# STM32_Brain.net
KiCad netlist of a schematic drawn in Altium Designer
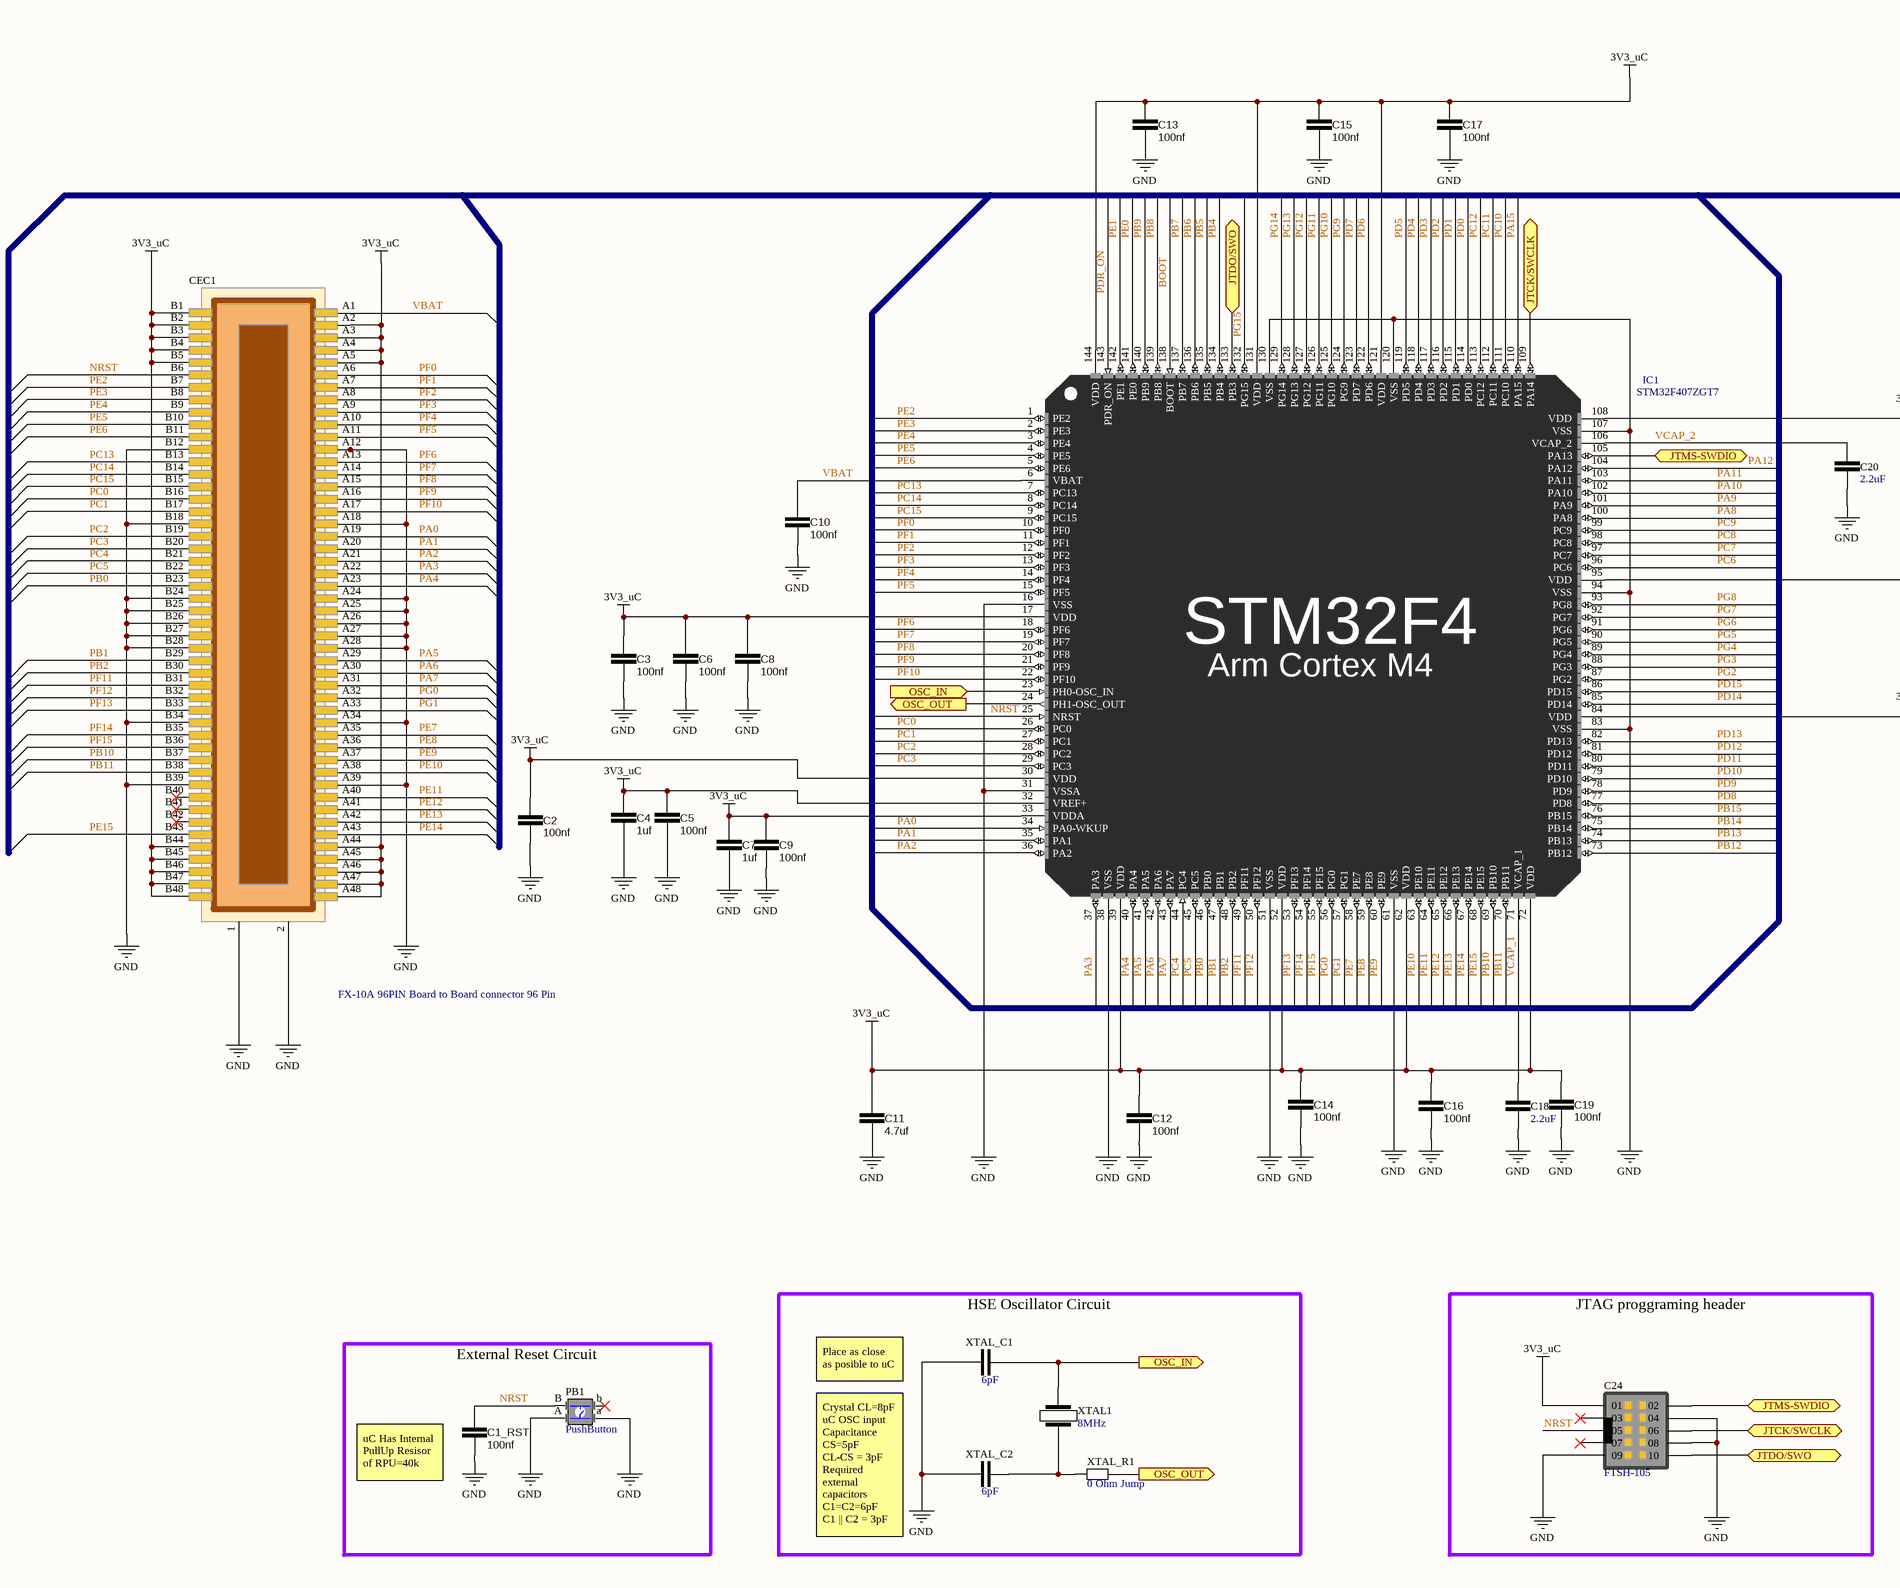
[diagram p0: STM32_Brain.SchDoc, left]
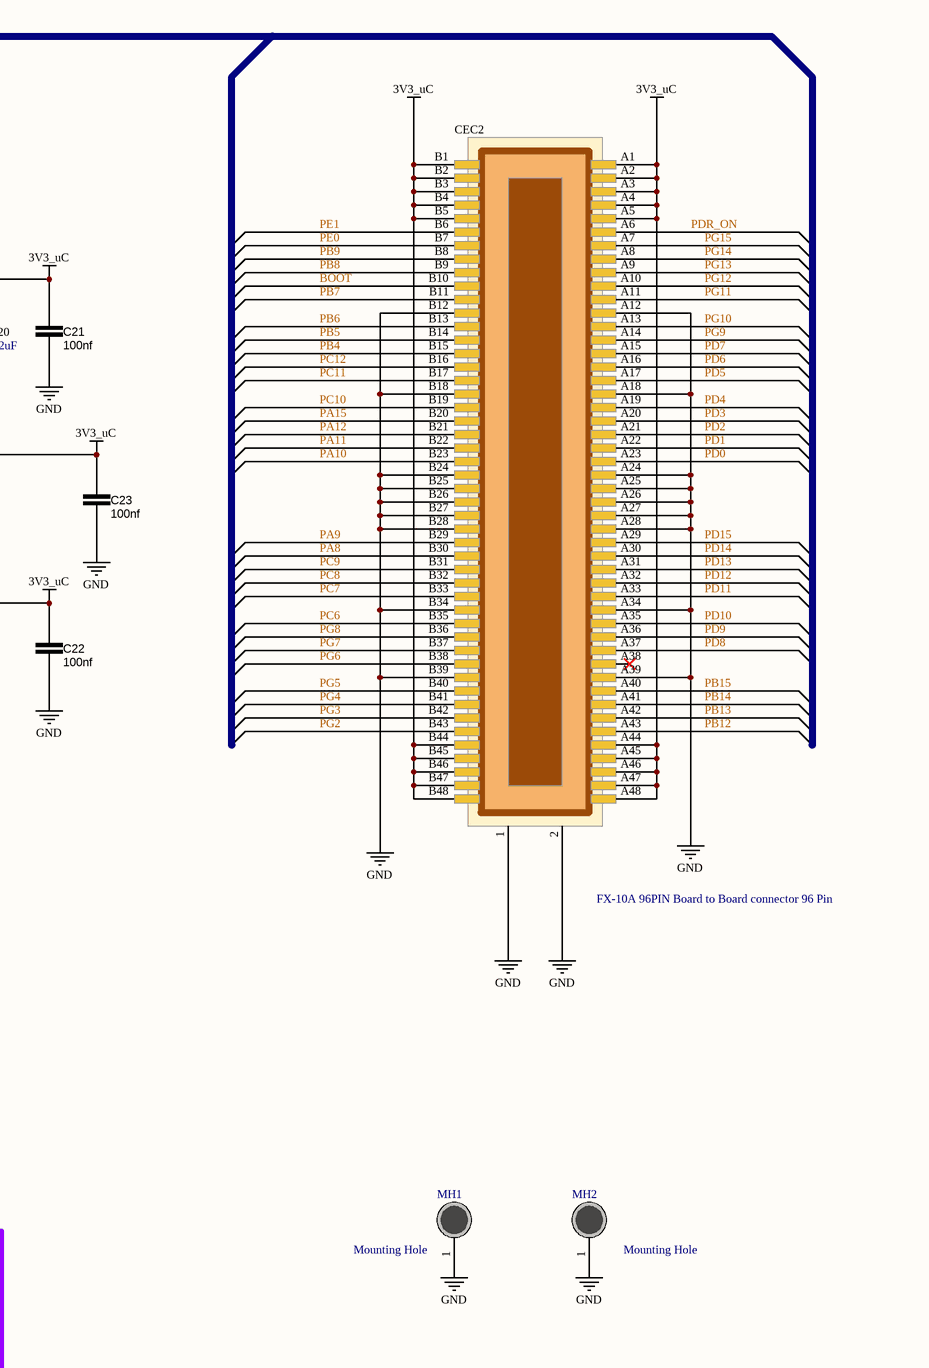
[diagram p1: STM32_Brain.SchDoc, right]

(export (version "E")
  (design (tool "Eeschema 10.0.6"))
  (components
    (comp (ref "C1_RST")
      (value "100nf")
      (footprint "CAP_0603")
      (description "CAP CER 100nF 0603 25V X7R")
      (libsource (lib "CapacitorsIntegrated") (part "0000007"))
    )
    (comp (ref "C2")
      (value "100nf")
      (footprint "CAP_0603")
      (description "CAP CER 100nF 0603 25V X7R")
      (libsource (lib "CapacitorsIntegrated") (part "0000007"))
    )
    (comp (ref "C3")
      (value "100nf")
      (footprint "CAP_0603")
      (description "CAP CER 100nF 0603 25V X7R")
      (libsource (lib "CapacitorsIntegrated") (part "0000007"))
    )
    (comp (ref "C4")
      (value "1uf")
      (footprint "CAP_0603")
      (description "CAP CER 1uF 0603 16V X7R")
      (fields (field (name "DIGIKEY PART NUMBER") "1276-1019-2-ND"))
      (libsource (lib "CapacitorsIntegrated") (part "0000009"))
    )
    (comp (ref "C5")
      (value "100nf")
      (footprint "CAP_0603")
      (description "CAP CER 100nF 0603 25V X7R")
      (libsource (lib "CapacitorsIntegrated") (part "0000007"))
    )
    (comp (ref "C6")
      (value "100nf")
      (footprint "CAP_0603")
      (description "CAP CER 100nF 0603 25V X7R")
      (libsource (lib "CapacitorsIntegrated") (part "0000007"))
    )
    (comp (ref "C7")
      (value "1uf")
      (footprint "CAP_0603")
      (description "CAP CER 1uF 0603 16V X7R")
      (fields (field (name "DIGIKEY PART NUMBER") "1276-1019-2-ND"))
      (libsource (lib "CapacitorsIntegrated") (part "0000009"))
    )
    (comp (ref "C8")
      (value "100nf")
      (footprint "CAP_0603")
      (description "CAP CER 100nF 0603 25V X7R")
      (libsource (lib "CapacitorsIntegrated") (part "0000007"))
    )
    (comp (ref "C9")
      (value "100nf")
      (footprint "CAP_0603")
      (description "CAP CER 100nF 0603 25V X7R")
      (libsource (lib "CapacitorsIntegrated") (part "0000007"))
    )
    (comp (ref "C10")
      (value "100nf")
      (footprint "CAP_0603")
      (description "CAP CER 100nF 0603 25V X7R")
      (libsource (lib "CapacitorsIntegrated") (part "0000007"))
    )
    (comp (ref "C11")
      (value "4.7uf")
      (footprint "CAP_0805")
      (description "CAP CER 4.7uF 0805 25V X5R")
      (libsource (lib "CapacitorsIntegrated") (part "0000003"))
    )
    (comp (ref "C12")
      (value "100nf")
      (footprint "CAP_0603")
      (description "CAP CER 100nF 0603 25V X7R")
      (libsource (lib "CapacitorsIntegrated") (part "0000007"))
    )
    (comp (ref "C13")
      (value "100nf")
      (footprint "CAP_0603")
      (description "CAP CER 100nF 0603 25V X7R")
      (libsource (lib "CapacitorsIntegrated") (part "0000007"))
    )
    (comp (ref "C14")
      (value "100nf")
      (footprint "CAP_0603")
      (description "CAP CER 100nF 0603 25V X7R")
      (libsource (lib "CapacitorsIntegrated") (part "0000007"))
    )
    (comp (ref "C15")
      (value "100nf")
      (footprint "CAP_0603")
      (description "CAP CER 100nF 0603 25V X7R")
      (libsource (lib "CapacitorsIntegrated") (part "0000007"))
    )
    (comp (ref "C16")
      (value "100nf")
      (footprint "CAP_0603")
      (description "CAP CER 100nF 0603 25V X7R")
      (libsource (lib "CapacitorsIntegrated") (part "0000007"))
    )
    (comp (ref "C17")
      (value "100nf")
      (footprint "CAP_0603")
      (description "CAP CER 100nF 0603 25V X7R")
      (libsource (lib "CapacitorsIntegrated") (part "0000007"))
    )
    (comp (ref "C18")
      (value "2.2uF")
      (footprint "CAP_0603")
      (description "CAP CER 2.2UF 16V X7S 0603")
      (fields (field (name "DIGIKEY PART NUMBER") "490-12731-1-ND"))
      (libsource (lib "CapacitorsIntegrated") (part "0000014"))
    )
    (comp (ref "C19")
      (value "100nf")
      (footprint "CAP_0603")
      (description "CAP CER 100nF 0603 25V X7R")
      (libsource (lib "CapacitorsIntegrated") (part "0000007"))
    )
    (comp (ref "C20")
      (value "2.2uF")
      (footprint "CAP_0603")
      (description "CAP CER 2.2UF 16V X7S 0603")
      (fields (field (name "DIGIKEY PART NUMBER") "490-12731-1-ND"))
      (libsource (lib "CapacitorsIntegrated") (part "0000014"))
    )
    (comp (ref "C21")
      (value "100nf")
      (footprint "CAP_0603")
      (description "CAP CER 100nF 0603 25V X7R")
      (libsource (lib "CapacitorsIntegrated") (part "0000007"))
    )
    (comp (ref "C22")
      (value "100nf")
      (footprint "CAP_0603")
      (description "CAP CER 100nF 0603 25V X7R")
      (libsource (lib "CapacitorsIntegrated") (part "0000007"))
    )
    (comp (ref "C23")
      (value "100nf")
      (footprint "CAP_0603")
      (description "CAP CER 100nF 0603 25V X7R")
      (libsource (lib "CapacitorsIntegrated") (part "0000007"))
    )
    (comp (ref "C24")
      (value "FTSH-105")
      (footprint "10 Position SMT Connector")
      (description "FTSH-105-01-F-DV-K - CONN HEADER SMD 10POS 1.27MM")
      (fields
        (field (name "DIGIKEY PART NUMBER") "SAM8796-ND")
        (field (name "MOUSER PART NUMBER") "200-FTSH10501LDVKPTR")
      )
      (libsource (lib "ElectroMechanical") (part "00000009"))
    )
    (comp (ref "CEC1")
      (value "FX-10A 96PIN Board to Board connector 96 Pin")
      (footprint "Board To Board Connector")
      (description "CONN RCPT 96POS SMD GOLD")
      (fields (field (name "DIGIKEY PART NUMBER") "H122463-ND"))
      (libsource (lib "ElectroMechanical") (part "00000008"))
    )
    (comp (ref "CEC2")
      (value "FX-10A 96PIN Board to Board connector 96 Pin")
      (footprint "Board To Board Connector")
      (description "CONN RCPT 96POS SMD GOLD")
      (fields (field (name "DIGIKEY PART NUMBER") "H122463-ND"))
      (libsource (lib "ElectroMechanical") (part "00000008"))
    )
    (comp (ref "IC1")
      (value "STM32F407ZGT7")
      (footprint "TSQFP50P2260X2260X160-144N")
      (libsource (lib "IntegratedCircuits") (part "STM32F407ZGT7"))
    )
    (comp (ref "MH1")
      (value "Mounting Hole")
      (footprint "HOLE-3mm")
      (description "Mounting Hole 3mm")
      (libsource (lib "ElectroMechanical") (part "00000006"))
    )
    (comp (ref "MH2")
      (value "Mounting Hole")
      (footprint "HOLE-3mm")
      (description "Mounting Hole 3mm")
      (libsource (lib "ElectroMechanical") (part "00000006"))
    )
    (comp (ref "PB1")
      (value "PushButton")
      (footprint "Tactile Switch")
      (description "SWITCH TACTILE SPST-NO 0.02A 15V")
      (fields (field (name "DIGIKEY PART NUMBER") "P12937SCT-ND"))
      (libsource (lib "ElectroMechanical") (part "00000010"))
    )
    (comp (ref "XTAL1")
      (value "8MHz")
      (footprint "XTAL-SMD")
      (description "CRYSTAL 8.0000MHZ 8PF SMD")
      (fields (field (name "DIGIKEY PART NUMBER") "644-STDCSU1-8MTR-ND"))
      (libsource (lib "Miscellaneous_Lib1") (part "00000004"))
    )
    (comp (ref "XTAL_C1")
      (value "6pF")
      (footprint "CAP_0402")
      (description "CAP CER 6PF 25V C0G/NP0 0402")
      (fields (field (name "DIGIKEY PART NUMBER") "399-CBR04C609D3GACCT-ND"))
      (libsource (lib "CapacitorsIntegrated") (part "0000016"))
    )
    (comp (ref "XTAL_C2")
      (value "6pF")
      (footprint "CAP_0402")
      (description "CAP CER 6PF 25V C0G/NP0 0402")
      (fields (field (name "DIGIKEY PART NUMBER") "399-CBR04C609D3GACCT-ND"))
      (libsource (lib "CapacitorsIntegrated") (part "0000016"))
    )
    (comp (ref "XTAL_R1")
      (value "0 Ohm Jump")
      (footprint "RES_0402")
      (description "RES SMD 0 OHM JUMPER 1/10W 0402")
      (fields (field (name "DIGIKEY PART NUMBER") "P0.0JCT-ND"))
      (libsource (lib "ResistorsIntegrated") (part "R000008"))
    )
  )
  (nets
    (net (code "1") (name "/BOOT") (class "Default")
      (node (ref "CEC2") (pin "B10") (pinfunction "10_B10") (pintype "passive"))
      (node (ref "IC1") (pin "138") (pinfunction "BOOT_138") (pintype "input"))
    )
    (net (code "2") (name "/JTCK{slash}SWCLK") (class "Default")
      (node (ref "C24") (pin "06") (pinfunction "06_06") (pintype "passive"))
      (node (ref "IC1") (pin "109") (pinfunction "PA14_109") (pintype "bidirectional"))
    )
    (net (code "3") (name "/JTDO{slash}SWO") (class "Default")
      (node (ref "C24") (pin "10") (pinfunction "10_10") (pintype "passive"))
      (node (ref "IC1") (pin "133") (pinfunction "PB3_133") (pintype "bidirectional"))
    )
    (net (code "4") (name "/JTMS-SWDIO") (class "Default")
      (node (ref "C24") (pin "02") (pinfunction "02_02") (pintype "passive"))
      (node (ref "IC1") (pin "105") (pinfunction "PA13_105") (pintype "bidirectional"))
    )
    (net (code "5") (name "/NRST") (class "Default")
      (node (ref "C1_RST") (pin "2") (pinfunction "2_2") (pintype "passive"))
      (node (ref "C24") (pin "05") (pinfunction "05_05") (pintype "passive"))
      (node (ref "CEC1") (pin "B6") (pinfunction "6_B6") (pintype "passive"))
      (node (ref "IC1") (pin "25") (pinfunction "NRST_25") (pintype "input"))
      (node (ref "PB1") (pin "B") (pinfunction "B_B") (pintype "passive"))
    )
    (net (code "6") (name "/OSC_IN") (class "Default")
      (node (ref "IC1") (pin "23") (pinfunction "PH0-OSC_IN_23") (pintype "input"))
      (node (ref "XTAL1") (pin "2") (pinfunction "2_2") (pintype "passive"))
      (node (ref "XTAL_C1") (pin "2") (pinfunction "2_2") (pintype "passive"))
    )
    (net (code "7") (name "/OSC_OUT") (class "Default")
      (node (ref "IC1") (pin "24") (pinfunction "PH1-OSC_OUT_24") (pintype "output"))
      (node (ref "XTAL_R1") (pin "2") (pinfunction "2_2") (pintype "passive"))
    )
    (net (code "8") (name "/PA0") (class "Default")
      (node (ref "CEC1") (pin "A19") (pinfunction "19_A19") (pintype "passive"))
      (node (ref "IC1") (pin "34") (pinfunction "PA0-WKUP_34") (pintype "input"))
    )
    (net (code "9") (name "/PA1") (class "Default")
      (node (ref "CEC1") (pin "A20") (pinfunction "20_A20") (pintype "passive"))
      (node (ref "IC1") (pin "35") (pinfunction "PA1_35") (pintype "bidirectional"))
    )
    (net (code "10") (name "/PA2") (class "Default")
      (node (ref "CEC1") (pin "A21") (pinfunction "21_A21") (pintype "passive"))
      (node (ref "IC1") (pin "36") (pinfunction "PA2_36") (pintype "bidirectional"))
    )
    (net (code "11") (name "/PA3") (class "Default")
      (node (ref "CEC1") (pin "A22") (pinfunction "22_A22") (pintype "passive"))
      (node (ref "IC1") (pin "37") (pinfunction "PA3_37") (pintype "bidirectional"))
    )
    (net (code "12") (name "/PA4") (class "Default")
      (node (ref "CEC1") (pin "A23") (pinfunction "23_A23") (pintype "passive"))
      (node (ref "IC1") (pin "40") (pinfunction "PA4_40") (pintype "bidirectional"))
    )
    (net (code "13") (name "/PA5") (class "Default")
      (node (ref "CEC1") (pin "A29") (pinfunction "29_A29") (pintype "passive"))
      (node (ref "IC1") (pin "41") (pinfunction "PA5_41") (pintype "bidirectional"))
    )
    (net (code "14") (name "/PA6") (class "Default")
      (node (ref "CEC1") (pin "A30") (pinfunction "30_A30") (pintype "passive"))
      (node (ref "IC1") (pin "42") (pinfunction "PA6_42") (pintype "bidirectional"))
    )
    (net (code "15") (name "/PA7") (class "Default")
      (node (ref "CEC1") (pin "A31") (pinfunction "31_A31") (pintype "passive"))
      (node (ref "IC1") (pin "43") (pinfunction "PA7_43") (pintype "bidirectional"))
    )
    (net (code "16") (name "/PA8") (class "Default")
      (node (ref "CEC2") (pin "B30") (pinfunction "30_B30") (pintype "passive"))
      (node (ref "IC1") (pin "100") (pinfunction "PA8_100") (pintype "bidirectional"))
    )
    (net (code "17") (name "/PA9") (class "Default")
      (node (ref "CEC2") (pin "B29") (pinfunction "29_B29") (pintype "passive"))
      (node (ref "IC1") (pin "101") (pinfunction "PA9_101") (pintype "bidirectional"))
    )
    (net (code "18") (name "/PA10") (class "Default")
      (node (ref "CEC2") (pin "B23") (pinfunction "23_B23") (pintype "passive"))
      (node (ref "IC1") (pin "102") (pinfunction "PA10_102") (pintype "bidirectional"))
    )
    (net (code "19") (name "/PA11") (class "Default")
      (node (ref "CEC2") (pin "B22") (pinfunction "22_B22") (pintype "passive"))
      (node (ref "IC1") (pin "103") (pinfunction "PA11_103") (pintype "bidirectional"))
    )
    (net (code "20") (name "/PA12") (class "Default")
      (node (ref "CEC2") (pin "B21") (pinfunction "21_B21") (pintype "passive"))
      (node (ref "IC1") (pin "104") (pinfunction "PA12_104") (pintype "bidirectional"))
    )
    (net (code "21") (name "/PA15") (class "Default")
      (node (ref "CEC2") (pin "B20") (pinfunction "20_B20") (pintype "passive"))
      (node (ref "IC1") (pin "110") (pinfunction "PA15_110") (pintype "bidirectional"))
    )
    (net (code "22") (name "/PB0") (class "Default")
      (node (ref "CEC1") (pin "B23") (pinfunction "23_B23") (pintype "passive"))
      (node (ref "IC1") (pin "46") (pinfunction "PB0_46") (pintype "bidirectional"))
    )
    (net (code "23") (name "/PB1") (class "Default")
      (node (ref "CEC1") (pin "B29") (pinfunction "29_B29") (pintype "passive"))
      (node (ref "IC1") (pin "47") (pinfunction "PB1_47") (pintype "bidirectional"))
    )
    (net (code "24") (name "/PB2") (class "Default")
      (node (ref "CEC1") (pin "B30") (pinfunction "30_B30") (pintype "passive"))
      (node (ref "IC1") (pin "48") (pinfunction "PB2_48") (pintype "bidirectional"))
    )
    (net (code "25") (name "/PB4") (class "Default")
      (node (ref "CEC2") (pin "B15") (pinfunction "15_B15") (pintype "passive"))
      (node (ref "IC1") (pin "134") (pinfunction "PB4_134") (pintype "bidirectional"))
    )
    (net (code "26") (name "/PB5") (class "Default")
      (node (ref "CEC2") (pin "B14") (pinfunction "14_B14") (pintype "passive"))
      (node (ref "IC1") (pin "135") (pinfunction "PB5_135") (pintype "bidirectional"))
    )
    (net (code "27") (name "/PB6") (class "Default")
      (node (ref "CEC2") (pin "B13") (pinfunction "13_B13") (pintype "passive"))
      (node (ref "IC1") (pin "136") (pinfunction "PB6_136") (pintype "bidirectional"))
    )
    (net (code "28") (name "/PB7") (class "Default")
      (node (ref "CEC2") (pin "B11") (pinfunction "11_B11") (pintype "passive"))
      (node (ref "IC1") (pin "137") (pinfunction "PB7_137") (pintype "bidirectional"))
    )
    (net (code "29") (name "/PB8") (class "Default")
      (node (ref "CEC2") (pin "B9") (pinfunction "9_B9") (pintype "passive"))
      (node (ref "IC1") (pin "139") (pinfunction "PB8_139") (pintype "bidirectional"))
    )
    (net (code "30") (name "/PB9") (class "Default")
      (node (ref "CEC2") (pin "B8") (pinfunction "8_B8") (pintype "passive"))
      (node (ref "IC1") (pin "140") (pinfunction "PB9_140") (pintype "bidirectional"))
    )
    (net (code "31") (name "/PB10") (class "Default")
      (node (ref "CEC1") (pin "B37") (pinfunction "37_B37") (pintype "passive"))
      (node (ref "IC1") (pin "69") (pinfunction "PB10_69") (pintype "bidirectional"))
    )
    (net (code "32") (name "/PB11") (class "Default")
      (node (ref "CEC1") (pin "B38") (pinfunction "38_B38") (pintype "passive"))
      (node (ref "IC1") (pin "70") (pinfunction "PB11_70") (pintype "bidirectional"))
    )
    (net (code "33") (name "/PB12") (class "Default")
      (node (ref "CEC2") (pin "A43") (pinfunction "43_A43") (pintype "passive"))
      (node (ref "IC1") (pin "73") (pinfunction "PB12_73") (pintype "bidirectional"))
    )
    (net (code "34") (name "/PB13") (class "Default")
      (node (ref "CEC2") (pin "A42") (pinfunction "42_A42") (pintype "passive"))
      (node (ref "IC1") (pin "74") (pinfunction "PB13_74") (pintype "bidirectional"))
    )
    (net (code "35") (name "/PB14") (class "Default")
      (node (ref "CEC2") (pin "A41") (pinfunction "41_A41") (pintype "passive"))
      (node (ref "IC1") (pin "75") (pinfunction "PB14_75") (pintype "bidirectional"))
    )
    (net (code "36") (name "/PB15") (class "Default")
      (node (ref "CEC2") (pin "A40") (pinfunction "40_A40") (pintype "passive"))
      (node (ref "IC1") (pin "76") (pinfunction "PB15_76") (pintype "bidirectional"))
    )
    (net (code "37") (name "/PC0") (class "Default")
      (node (ref "CEC1") (pin "B16") (pinfunction "16_B16") (pintype "passive"))
      (node (ref "IC1") (pin "26") (pinfunction "PC0_26") (pintype "bidirectional"))
    )
    (net (code "38") (name "/PC1") (class "Default")
      (node (ref "CEC1") (pin "B17") (pinfunction "17_B17") (pintype "passive"))
      (node (ref "IC1") (pin "27") (pinfunction "PC1_27") (pintype "bidirectional"))
    )
    (net (code "39") (name "/PC2") (class "Default")
      (node (ref "CEC1") (pin "B19") (pinfunction "19_B19") (pintype "passive"))
      (node (ref "IC1") (pin "28") (pinfunction "PC2_28") (pintype "bidirectional"))
    )
    (net (code "40") (name "/PC3") (class "Default")
      (node (ref "CEC1") (pin "B20") (pinfunction "20_B20") (pintype "passive"))
      (node (ref "IC1") (pin "29") (pinfunction "PC3_29") (pintype "bidirectional"))
    )
    (net (code "41") (name "/PC4") (class "Default")
      (node (ref "CEC1") (pin "B21") (pinfunction "21_B21") (pintype "passive"))
      (node (ref "IC1") (pin "44") (pinfunction "PC4_44") (pintype "input"))
    )
    (net (code "42") (name "/PC5") (class "Default")
      (node (ref "CEC1") (pin "B22") (pinfunction "22_B22") (pintype "passive"))
      (node (ref "IC1") (pin "45") (pinfunction "PC5_45") (pintype "bidirectional"))
    )
    (net (code "43") (name "/PC6") (class "Default")
      (node (ref "CEC2") (pin "B35") (pinfunction "35_B35") (pintype "passive"))
      (node (ref "IC1") (pin "96") (pinfunction "PC6_96") (pintype "bidirectional"))
    )
    (net (code "44") (name "/PC7") (class "Default")
      (node (ref "CEC2") (pin "B33") (pinfunction "33_B33") (pintype "passive"))
      (node (ref "IC1") (pin "97") (pinfunction "PC7_97") (pintype "bidirectional"))
    )
    (net (code "45") (name "/PC8") (class "Default")
      (node (ref "CEC2") (pin "B32") (pinfunction "32_B32") (pintype "passive"))
      (node (ref "IC1") (pin "98") (pinfunction "PC8_98") (pintype "bidirectional"))
    )
    (net (code "46") (name "/PC9") (class "Default")
      (node (ref "CEC2") (pin "B31") (pinfunction "31_B31") (pintype "passive"))
      (node (ref "IC1") (pin "99") (pinfunction "PC9_99") (pintype "bidirectional"))
    )
    (net (code "47") (name "/PC10") (class "Default")
      (node (ref "CEC2") (pin "B19") (pinfunction "19_B19") (pintype "passive"))
      (node (ref "IC1") (pin "111") (pinfunction "PC10_111") (pintype "bidirectional"))
    )
    (net (code "48") (name "/PC11") (class "Default")
      (node (ref "CEC2") (pin "B17") (pinfunction "17_B17") (pintype "passive"))
      (node (ref "IC1") (pin "112") (pinfunction "PC11_112") (pintype "bidirectional"))
    )
    (net (code "49") (name "/PC12") (class "Default")
      (node (ref "CEC2") (pin "B16") (pinfunction "16_B16") (pintype "passive"))
      (node (ref "IC1") (pin "113") (pinfunction "PC12_113") (pintype "bidirectional"))
    )
    (net (code "50") (name "/PC13") (class "Default")
      (node (ref "CEC1") (pin "B13") (pinfunction "13_B13") (pintype "passive"))
      (node (ref "IC1") (pin "7") (pinfunction "PC13_7") (pintype "bidirectional"))
    )
    (net (code "51") (name "/PC14") (class "Default")
      (node (ref "CEC1") (pin "B14") (pinfunction "14_B14") (pintype "passive"))
      (node (ref "IC1") (pin "8") (pinfunction "PC14_8") (pintype "bidirectional"))
    )
    (net (code "52") (name "/PC15") (class "Default")
      (node (ref "CEC1") (pin "B15") (pinfunction "15_B15") (pintype "passive"))
      (node (ref "IC1") (pin "9") (pinfunction "PC15_9") (pintype "bidirectional"))
    )
    (net (code "53") (name "/PD0") (class "Default")
      (node (ref "CEC2") (pin "A23") (pinfunction "23_A23") (pintype "passive"))
      (node (ref "IC1") (pin "114") (pinfunction "PD0_114") (pintype "bidirectional"))
    )
    (net (code "54") (name "/PD1") (class "Default")
      (node (ref "CEC2") (pin "A22") (pinfunction "22_A22") (pintype "passive"))
      (node (ref "IC1") (pin "115") (pinfunction "PD1_115") (pintype "bidirectional"))
    )
    (net (code "55") (name "/PD2") (class "Default")
      (node (ref "CEC2") (pin "A21") (pinfunction "21_A21") (pintype "passive"))
      (node (ref "IC1") (pin "116") (pinfunction "PD2_116") (pintype "bidirectional"))
    )
    (net (code "56") (name "/PD3") (class "Default")
      (node (ref "CEC2") (pin "A20") (pinfunction "20_A20") (pintype "passive"))
      (node (ref "IC1") (pin "117") (pinfunction "PD3_117") (pintype "bidirectional"))
    )
    (net (code "57") (name "/PD4") (class "Default")
      (node (ref "CEC2") (pin "A19") (pinfunction "19_A19") (pintype "passive"))
      (node (ref "IC1") (pin "118") (pinfunction "PD4_118") (pintype "bidirectional"))
    )
    (net (code "58") (name "/PD5") (class "Default")
      (node (ref "CEC2") (pin "A17") (pinfunction "17_A17") (pintype "passive"))
      (node (ref "IC1") (pin "119") (pinfunction "PD5_119") (pintype "bidirectional"))
    )
    (net (code "59") (name "/PD6") (class "Default")
      (node (ref "CEC2") (pin "A16") (pinfunction "16_A16") (pintype "passive"))
      (node (ref "IC1") (pin "122") (pinfunction "PD6_122") (pintype "bidirectional"))
    )
    (net (code "60") (name "/PD7") (class "Default")
      (node (ref "CEC2") (pin "A15") (pinfunction "15_A15") (pintype "passive"))
      (node (ref "IC1") (pin "123") (pinfunction "PD7_123") (pintype "bidirectional"))
    )
    (net (code "61") (name "/PD8") (class "Default")
      (node (ref "CEC2") (pin "A37") (pinfunction "37_A37") (pintype "passive"))
      (node (ref "IC1") (pin "77") (pinfunction "PD8_77") (pintype "bidirectional"))
    )
    (net (code "62") (name "/PD9") (class "Default")
      (node (ref "CEC2") (pin "A36") (pinfunction "36_A36") (pintype "passive"))
      (node (ref "IC1") (pin "78") (pinfunction "PD9_78") (pintype "bidirectional"))
    )
    (net (code "63") (name "/PD10") (class "Default")
      (node (ref "CEC2") (pin "A35") (pinfunction "35_A35") (pintype "passive"))
      (node (ref "IC1") (pin "79") (pinfunction "PD10_79") (pintype "bidirectional"))
    )
    (net (code "64") (name "/PD11") (class "Default")
      (node (ref "CEC2") (pin "A33") (pinfunction "33_A33") (pintype "passive"))
      (node (ref "IC1") (pin "80") (pinfunction "PD11_80") (pintype "bidirectional"))
    )
    (net (code "65") (name "/PD12") (class "Default")
      (node (ref "CEC2") (pin "A32") (pinfunction "32_A32") (pintype "passive"))
      (node (ref "IC1") (pin "81") (pinfunction "PD12_81") (pintype "bidirectional"))
    )
    (net (code "66") (name "/PD13") (class "Default")
      (node (ref "CEC2") (pin "A31") (pinfunction "31_A31") (pintype "passive"))
      (node (ref "IC1") (pin "82") (pinfunction "PD13_82") (pintype "bidirectional"))
    )
    (net (code "67") (name "/PD14") (class "Default")
      (node (ref "CEC2") (pin "A30") (pinfunction "30_A30") (pintype "passive"))
      (node (ref "IC1") (pin "85") (pinfunction "PD14_85") (pintype "bidirectional"))
    )
    (net (code "68") (name "/PD15") (class "Default")
      (node (ref "CEC2") (pin "A29") (pinfunction "29_A29") (pintype "passive"))
      (node (ref "IC1") (pin "86") (pinfunction "PD15_86") (pintype "bidirectional"))
    )
    (net (code "69") (name "/PDR_ON") (class "Default")
      (node (ref "CEC2") (pin "A6") (pinfunction "6_A6") (pintype "passive"))
      (node (ref "IC1") (pin "143") (pinfunction "PDR_ON_143") (pintype "input"))
    )
    (net (code "70") (name "/PE0") (class "Default")
      (node (ref "CEC2") (pin "B7") (pinfunction "7_B7") (pintype "passive"))
      (node (ref "IC1") (pin "141") (pinfunction "PE0_141") (pintype "bidirectional"))
    )
    (net (code "71") (name "/PE1") (class "Default")
      (node (ref "CEC2") (pin "B6") (pinfunction "6_B6") (pintype "passive"))
      (node (ref "IC1") (pin "142") (pinfunction "PE1_142") (pintype "bidirectional"))
    )
    (net (code "72") (name "/PE2") (class "Default")
      (node (ref "CEC1") (pin "B7") (pinfunction "7_B7") (pintype "passive"))
      (node (ref "IC1") (pin "1") (pinfunction "PE2_1") (pintype "bidirectional"))
    )
    (net (code "73") (name "/PE3") (class "Default")
      (node (ref "CEC1") (pin "B8") (pinfunction "8_B8") (pintype "passive"))
      (node (ref "IC1") (pin "2") (pinfunction "PE3_2") (pintype "bidirectional"))
    )
    (net (code "74") (name "/PE4") (class "Default")
      (node (ref "CEC1") (pin "B9") (pinfunction "9_B9") (pintype "passive"))
      (node (ref "IC1") (pin "3") (pinfunction "PE4_3") (pintype "bidirectional"))
    )
    (net (code "75") (name "/PE5") (class "Default")
      (node (ref "CEC1") (pin "B10") (pinfunction "10_B10") (pintype "passive"))
      (node (ref "IC1") (pin "4") (pinfunction "PE5_4") (pintype "bidirectional"))
    )
    (net (code "76") (name "/PE6") (class "Default")
      (node (ref "CEC1") (pin "B11") (pinfunction "11_B11") (pintype "passive"))
      (node (ref "IC1") (pin "5") (pinfunction "PE6_5") (pintype "bidirectional"))
    )
    (net (code "77") (name "/PE7") (class "Default")
      (node (ref "CEC1") (pin "A35") (pinfunction "35_A35") (pintype "passive"))
      (node (ref "IC1") (pin "58") (pinfunction "PE7_58") (pintype "bidirectional"))
    )
    (net (code "78") (name "/PE8") (class "Default")
      (node (ref "CEC1") (pin "A36") (pinfunction "36_A36") (pintype "passive"))
      (node (ref "IC1") (pin "59") (pinfunction "PE8_59") (pintype "bidirectional"))
    )
    (net (code "79") (name "/PE9") (class "Default")
      (node (ref "CEC1") (pin "A37") (pinfunction "37_A37") (pintype "passive"))
      (node (ref "IC1") (pin "60") (pinfunction "PE9_60") (pintype "bidirectional"))
    )
    (net (code "80") (name "/PE10") (class "Default")
      (node (ref "CEC1") (pin "A38") (pinfunction "38_A38") (pintype "passive"))
      (node (ref "IC1") (pin "63") (pinfunction "PE10_63") (pintype "bidirectional"))
    )
    (net (code "81") (name "/PE11") (class "Default")
      (node (ref "CEC1") (pin "A40") (pinfunction "40_A40") (pintype "passive"))
      (node (ref "IC1") (pin "64") (pinfunction "PE11_64") (pintype "bidirectional"))
    )
    (net (code "82") (name "/PE12") (class "Default")
      (node (ref "CEC1") (pin "A41") (pinfunction "41_A41") (pintype "passive"))
      (node (ref "IC1") (pin "65") (pinfunction "PE12_65") (pintype "bidirectional"))
    )
    (net (code "83") (name "/PE13") (class "Default")
      (node (ref "CEC1") (pin "A42") (pinfunction "42_A42") (pintype "passive"))
      (node (ref "IC1") (pin "66") (pinfunction "PE13_66") (pintype "bidirectional"))
    )
    (net (code "84") (name "/PE14") (class "Default")
      (node (ref "CEC1") (pin "A43") (pinfunction "43_A43") (pintype "passive"))
      (node (ref "IC1") (pin "67") (pinfunction "PE14_67") (pintype "bidirectional"))
    )
    (net (code "85") (name "/PE15") (class "Default")
      (node (ref "CEC1") (pin "B43") (pinfunction "43_B43") (pintype "passive"))
      (node (ref "IC1") (pin "68") (pinfunction "PE15_68") (pintype "bidirectional"))
    )
    (net (code "86") (name "/PF0") (class "Default")
      (node (ref "CEC1") (pin "A6") (pinfunction "6_A6") (pintype "passive"))
      (node (ref "IC1") (pin "10") (pinfunction "PF0_10") (pintype "bidirectional"))
    )
    (net (code "87") (name "/PF1") (class "Default")
      (node (ref "CEC1") (pin "A7") (pinfunction "7_A7") (pintype "passive"))
      (node (ref "IC1") (pin "11") (pinfunction "PF1_11") (pintype "bidirectional"))
    )
    (net (code "88") (name "/PF2") (class "Default")
      (node (ref "CEC1") (pin "A8") (pinfunction "8_A8") (pintype "passive"))
      (node (ref "IC1") (pin "12") (pinfunction "PF2_12") (pintype "bidirectional"))
    )
    (net (code "89") (name "/PF3") (class "Default")
      (node (ref "CEC1") (pin "A9") (pinfunction "9_A9") (pintype "passive"))
      (node (ref "IC1") (pin "13") (pinfunction "PF3_13") (pintype "bidirectional"))
    )
    (net (code "90") (name "/PF4") (class "Default")
      (node (ref "CEC1") (pin "A10") (pinfunction "10_A10") (pintype "passive"))
      (node (ref "IC1") (pin "14") (pinfunction "PF4_14") (pintype "bidirectional"))
    )
    (net (code "91") (name "/PF5") (class "Default")
      (node (ref "CEC1") (pin "A11") (pinfunction "11_A11") (pintype "passive"))
      (node (ref "IC1") (pin "15") (pinfunction "PF5_15") (pintype "bidirectional"))
    )
    (net (code "92") (name "/PF6") (class "Default")
      (node (ref "CEC1") (pin "A13") (pinfunction "13_A13") (pintype "passive"))
      (node (ref "IC1") (pin "18") (pinfunction "PF6_18") (pintype "bidirectional"))
    )
    (net (code "93") (name "/PF7") (class "Default")
      (node (ref "CEC1") (pin "A14") (pinfunction "14_A14") (pintype "passive"))
      (node (ref "IC1") (pin "19") (pinfunction "PF7_19") (pintype "bidirectional"))
    )
    (net (code "94") (name "/PF8") (class "Default")
      (node (ref "CEC1") (pin "A15") (pinfunction "15_A15") (pintype "passive"))
      (node (ref "IC1") (pin "20") (pinfunction "PF8_20") (pintype "bidirectional"))
    )
    (net (code "95") (name "/PF9") (class "Default")
      (node (ref "CEC1") (pin "A16") (pinfunction "16_A16") (pintype "passive"))
      (node (ref "IC1") (pin "21") (pinfunction "PF9_21") (pintype "bidirectional"))
    )
    (net (code "96") (name "/PF10") (class "Default")
      (node (ref "CEC1") (pin "A17") (pinfunction "17_A17") (pintype "passive"))
      (node (ref "IC1") (pin "22") (pinfunction "PF10_22") (pintype "bidirectional"))
    )
    (net (code "97") (name "/PF11") (class "Default")
      (node (ref "CEC1") (pin "B31") (pinfunction "31_B31") (pintype "passive"))
      (node (ref "IC1") (pin "49") (pinfunction "PF11_49") (pintype "bidirectional"))
    )
    (net (code "98") (name "/PF12") (class "Default")
      (node (ref "CEC1") (pin "B32") (pinfunction "32_B32") (pintype "passive"))
      (node (ref "IC1") (pin "50") (pinfunction "PF12_50") (pintype "bidirectional"))
    )
    (net (code "99") (name "/PF13") (class "Default")
      (node (ref "CEC1") (pin "B33") (pinfunction "33_B33") (pintype "passive"))
      (node (ref "IC1") (pin "53") (pinfunction "PF13_53") (pintype "bidirectional"))
    )
    (net (code "100") (name "/PF14") (class "Default")
      (node (ref "CEC1") (pin "B35") (pinfunction "35_B35") (pintype "passive"))
      (node (ref "IC1") (pin "54") (pinfunction "PF14_54") (pintype "bidirectional"))
    )
    (net (code "101") (name "/PF15") (class "Default")
      (node (ref "CEC1") (pin "B36") (pinfunction "36_B36") (pintype "passive"))
      (node (ref "IC1") (pin "55") (pinfunction "PF15_55") (pintype "bidirectional"))
    )
    (net (code "102") (name "/PG0") (class "Default")
      (node (ref "CEC1") (pin "A32") (pinfunction "32_A32") (pintype "passive"))
      (node (ref "IC1") (pin "56") (pinfunction "PG0_56") (pintype "bidirectional"))
    )
    (net (code "103") (name "/PG1") (class "Default")
      (node (ref "CEC1") (pin "A33") (pinfunction "33_A33") (pintype "passive"))
      (node (ref "IC1") (pin "57") (pinfunction "PG1_57") (pintype "bidirectional"))
    )
    (net (code "104") (name "/PG2") (class "Default")
      (node (ref "CEC2") (pin "B43") (pinfunction "43_B43") (pintype "passive"))
      (node (ref "IC1") (pin "87") (pinfunction "PG2_87") (pintype "bidirectional"))
    )
    (net (code "105") (name "/PG3") (class "Default")
      (node (ref "CEC2") (pin "B42") (pinfunction "42_B42") (pintype "passive"))
      (node (ref "IC1") (pin "88") (pinfunction "PG3_88") (pintype "bidirectional"))
    )
    (net (code "106") (name "/PG4") (class "Default")
      (node (ref "CEC2") (pin "B41") (pinfunction "41_B41") (pintype "passive"))
      (node (ref "IC1") (pin "89") (pinfunction "PG4_89") (pintype "bidirectional"))
    )
    (net (code "107") (name "/PG5") (class "Default")
      (node (ref "CEC2") (pin "B40") (pinfunction "40_B40") (pintype "passive"))
      (node (ref "IC1") (pin "90") (pinfunction "PG5_90") (pintype "bidirectional"))
    )
    (net (code "108") (name "/PG6") (class "Default")
      (node (ref "CEC2") (pin "B38") (pinfunction "38_B38") (pintype "passive"))
      (node (ref "IC1") (pin "91") (pinfunction "PG6_91") (pintype "bidirectional"))
    )
    (net (code "109") (name "/PG7") (class "Default")
      (node (ref "CEC2") (pin "B37") (pinfunction "37_B37") (pintype "passive"))
      (node (ref "IC1") (pin "92") (pinfunction "PG7_92") (pintype "bidirectional"))
    )
    (net (code "110") (name "/PG8") (class "Default")
      (node (ref "CEC2") (pin "B36") (pinfunction "36_B36") (pintype "passive"))
      (node (ref "IC1") (pin "93") (pinfunction "PG8_93") (pintype "bidirectional"))
    )
    (net (code "111") (name "/PG9") (class "Default")
      (node (ref "CEC2") (pin "A14") (pinfunction "14_A14") (pintype "passive"))
      (node (ref "IC1") (pin "124") (pinfunction "PG9_124") (pintype "bidirectional"))
    )
    (net (code "112") (name "/PG10") (class "Default")
      (node (ref "CEC2") (pin "A13") (pinfunction "13_A13") (pintype "passive"))
      (node (ref "IC1") (pin "125") (pinfunction "PG10_125") (pintype "bidirectional"))
    )
    (net (code "113") (name "/PG11") (class "Default")
      (node (ref "CEC2") (pin "A11") (pinfunction "11_A11") (pintype "passive"))
      (node (ref "IC1") (pin "126") (pinfunction "PG11_126") (pintype "bidirectional"))
    )
    (net (code "114") (name "/PG12") (class "Default")
      (node (ref "CEC2") (pin "A10") (pinfunction "10_A10") (pintype "passive"))
      (node (ref "IC1") (pin "127") (pinfunction "PG12_127") (pintype "bidirectional"))
    )
    (net (code "115") (name "/PG13") (class "Default")
      (node (ref "CEC2") (pin "A9") (pinfunction "9_A9") (pintype "passive"))
      (node (ref "IC1") (pin "128") (pinfunction "PG13_128") (pintype "bidirectional"))
    )
    (net (code "116") (name "/PG14") (class "Default")
      (node (ref "CEC2") (pin "A8") (pinfunction "8_A8") (pintype "passive"))
      (node (ref "IC1") (pin "129") (pinfunction "PG14_129") (pintype "bidirectional"))
    )
    (net (code "117") (name "/PG15") (class "Default")
      (node (ref "CEC2") (pin "A7") (pinfunction "7_A7") (pintype "passive"))
      (node (ref "IC1") (pin "132") (pinfunction "PG15_132") (pintype "bidirectional"))
    )
    (net (code "118") (name "/VBAT") (class "Default")
      (node (ref "C10") (pin "2") (pinfunction "2_2") (pintype "passive"))
      (node (ref "CEC1") (pin "A1") (pinfunction "1_A1") (pintype "passive"))
      (node (ref "IC1") (pin "6") (pinfunction "VBAT_6") (pintype "power_in"))
    )
    (net (code "119") (name "/VCAP_1") (class "Default")
      (node (ref "C18") (pin "2") (pinfunction "2_2") (pintype "passive"))
      (node (ref "IC1") (pin "71") (pinfunction "VCAP_1_71") (pintype "power_in"))
    )
    (net (code "120") (name "/VCAP_2") (class "Default")
      (node (ref "C20") (pin "2") (pinfunction "2_2") (pintype "passive"))
      (node (ref "IC1") (pin "106") (pinfunction "VCAP_2_106") (pintype "power_in"))
    )
    (net (code "121") (name "3V3_uC") (class "Default")
      (node (ref "C11") (pin "2") (pinfunction "2_2") (pintype "passive"))
      (node (ref "C12") (pin "2") (pinfunction "2_2") (pintype "passive"))
      (node (ref "C13") (pin "2") (pinfunction "2_2") (pintype "passive"))
      (node (ref "C14") (pin "2") (pinfunction "2_2") (pintype "passive"))
      (node (ref "C15") (pin "2") (pinfunction "2_2") (pintype "passive"))
      (node (ref "C16") (pin "2") (pinfunction "2_2") (pintype "passive"))
      (node (ref "C17") (pin "2") (pinfunction "2_2") (pintype "passive"))
      (node (ref "C19") (pin "2") (pinfunction "2_2") (pintype "passive"))
      (node (ref "C2") (pin "2") (pinfunction "2_2") (pintype "passive"))
      (node (ref "C21") (pin "2") (pinfunction "2_2") (pintype "passive"))
      (node (ref "C22") (pin "2") (pinfunction "2_2") (pintype "passive"))
      (node (ref "C23") (pin "2") (pinfunction "2_2") (pintype "passive"))
      (node (ref "C24") (pin "01") (pinfunction "01_01") (pintype "passive"))
      (node (ref "C3") (pin "2") (pinfunction "2_2") (pintype "passive"))
      (node (ref "C4") (pin "2") (pinfunction "2_2") (pintype "passive"))
      (node (ref "C5") (pin "2") (pinfunction "2_2") (pintype "passive"))
      (node (ref "C6") (pin "2") (pinfunction "2_2") (pintype "passive"))
      (node (ref "C7") (pin "2") (pinfunction "2_2") (pintype "passive"))
      (node (ref "C8") (pin "2") (pinfunction "2_2") (pintype "passive"))
      (node (ref "C9") (pin "2") (pinfunction "2_2") (pintype "passive"))
      (node (ref "CEC1") (pin "A2") (pinfunction "2_A2") (pintype "passive"))
      (node (ref "CEC1") (pin "A3") (pinfunction "3_A3") (pintype "passive"))
      (node (ref "CEC1") (pin "A4") (pinfunction "4_A4") (pintype "passive"))
      (node (ref "CEC1") (pin "A44") (pinfunction "44_A44") (pintype "passive"))
      (node (ref "CEC1") (pin "A45") (pinfunction "45_A45") (pintype "passive"))
      (node (ref "CEC1") (pin "A46") (pinfunction "46_A46") (pintype "passive"))
      (node (ref "CEC1") (pin "A47") (pinfunction "47_A47") (pintype "passive"))
      (node (ref "CEC1") (pin "A48") (pinfunction "48_A48") (pintype "passive"))
      (node (ref "CEC1") (pin "A5") (pinfunction "5_A5") (pintype "passive"))
      (node (ref "CEC1") (pin "B1") (pinfunction "1_B1") (pintype "passive"))
      (node (ref "CEC1") (pin "B2") (pinfunction "2_B2") (pintype "passive"))
      (node (ref "CEC1") (pin "B3") (pinfunction "3_B3") (pintype "passive"))
      (node (ref "CEC1") (pin "B4") (pinfunction "4_B4") (pintype "passive"))
      (node (ref "CEC1") (pin "B44") (pinfunction "44_B44") (pintype "passive"))
      (node (ref "CEC1") (pin "B45") (pinfunction "45_B45") (pintype "passive"))
      (node (ref "CEC1") (pin "B46") (pinfunction "46_B46") (pintype "passive"))
      (node (ref "CEC1") (pin "B47") (pinfunction "47_B47") (pintype "passive"))
      (node (ref "CEC1") (pin "B48") (pinfunction "48_B48") (pintype "passive"))
      (node (ref "CEC1") (pin "B5") (pinfunction "5_B5") (pintype "passive"))
      (node (ref "CEC2") (pin "A1") (pinfunction "1_A1") (pintype "passive"))
      (node (ref "CEC2") (pin "A2") (pinfunction "2_A2") (pintype "passive"))
      (node (ref "CEC2") (pin "A3") (pinfunction "3_A3") (pintype "passive"))
      (node (ref "CEC2") (pin "A4") (pinfunction "4_A4") (pintype "passive"))
      (node (ref "CEC2") (pin "A44") (pinfunction "44_A44") (pintype "passive"))
      (node (ref "CEC2") (pin "A45") (pinfunction "45_A45") (pintype "passive"))
      (node (ref "CEC2") (pin "A46") (pinfunction "46_A46") (pintype "passive"))
      (node (ref "CEC2") (pin "A47") (pinfunction "47_A47") (pintype "passive"))
      (node (ref "CEC2") (pin "A48") (pinfunction "48_A48") (pintype "passive"))
      (node (ref "CEC2") (pin "A5") (pinfunction "5_A5") (pintype "passive"))
      (node (ref "CEC2") (pin "B1") (pinfunction "1_B1") (pintype "passive"))
      (node (ref "CEC2") (pin "B2") (pinfunction "2_B2") (pintype "passive"))
      (node (ref "CEC2") (pin "B3") (pinfunction "3_B3") (pintype "passive"))
      (node (ref "CEC2") (pin "B4") (pinfunction "4_B4") (pintype "passive"))
      (node (ref "CEC2") (pin "B44") (pinfunction "44_B44") (pintype "passive"))
      (node (ref "CEC2") (pin "B45") (pinfunction "45_B45") (pintype "passive"))
      (node (ref "CEC2") (pin "B46") (pinfunction "46_B46") (pintype "passive"))
      (node (ref "CEC2") (pin "B47") (pinfunction "47_B47") (pintype "passive"))
      (node (ref "CEC2") (pin "B48") (pinfunction "48_B48") (pintype "passive"))
      (node (ref "CEC2") (pin "B5") (pinfunction "5_B5") (pintype "passive"))
      (node (ref "IC1") (pin "108") (pinfunction "VDD_108") (pintype "power_in"))
      (node (ref "IC1") (pin "121") (pinfunction "VDD_121") (pintype "power_in"))
      (node (ref "IC1") (pin "131") (pinfunction "VDD_131") (pintype "power_in"))
      (node (ref "IC1") (pin "144") (pinfunction "VDD_144") (pintype "power_in"))
      (node (ref "IC1") (pin "17") (pinfunction "VDD_17") (pintype "power_in"))
      (node (ref "IC1") (pin "30") (pinfunction "VDD_30") (pintype "power_in"))
      (node (ref "IC1") (pin "32") (pinfunction "VREF+_32") (pintype "power_in"))
      (node (ref "IC1") (pin "33") (pinfunction "VDDA_33") (pintype "power_in"))
      (node (ref "IC1") (pin "39") (pinfunction "VDD_39") (pintype "power_in"))
      (node (ref "IC1") (pin "52") (pinfunction "VDD_52") (pintype "power_in"))
      (node (ref "IC1") (pin "62") (pinfunction "VDD_62") (pintype "power_in"))
      (node (ref "IC1") (pin "72") (pinfunction "VDD_72") (pintype "power_in"))
      (node (ref "IC1") (pin "84") (pinfunction "VDD_84") (pintype "power_in"))
      (node (ref "IC1") (pin "95") (pinfunction "VDD_95") (pintype "power_in"))
    )
    (net (code "122") (name "GND") (class "Default")
      (node (ref "C10") (pin "1") (pinfunction "1_1") (pintype "passive"))
      (node (ref "C11") (pin "1") (pinfunction "1_1") (pintype "passive"))
      (node (ref "C12") (pin "1") (pinfunction "1_1") (pintype "passive"))
      (node (ref "C13") (pin "1") (pinfunction "1_1") (pintype "passive"))
      (node (ref "C14") (pin "1") (pinfunction "1_1") (pintype "passive"))
      (node (ref "C15") (pin "1") (pinfunction "1_1") (pintype "passive"))
      (node (ref "C16") (pin "1") (pinfunction "1_1") (pintype "passive"))
      (node (ref "C17") (pin "1") (pinfunction "1_1") (pintype "passive"))
      (node (ref "C18") (pin "1") (pinfunction "1_1") (pintype "passive"))
      (node (ref "C19") (pin "1") (pinfunction "1_1") (pintype "passive"))
      (node (ref "C1_RST") (pin "1") (pinfunction "1_1") (pintype "passive"))
      (node (ref "C2") (pin "1") (pinfunction "1_1") (pintype "passive"))
      (node (ref "C20") (pin "1") (pinfunction "1_1") (pintype "passive"))
      (node (ref "C21") (pin "1") (pinfunction "1_1") (pintype "passive"))
      (node (ref "C22") (pin "1") (pinfunction "1_1") (pintype "passive"))
      (node (ref "C23") (pin "1") (pinfunction "1_1") (pintype "passive"))
      (node (ref "C24") (pin "04") (pinfunction "04_04") (pintype "passive"))
      (node (ref "C24") (pin "08") (pinfunction "08_08") (pintype "passive"))
      (node (ref "C24") (pin "09") (pinfunction "09_09") (pintype "passive"))
      (node (ref "C3") (pin "1") (pinfunction "1_1") (pintype "passive"))
      (node (ref "C4") (pin "1") (pinfunction "1_1") (pintype "passive"))
      (node (ref "C5") (pin "1") (pinfunction "1_1") (pintype "passive"))
      (node (ref "C6") (pin "1") (pinfunction "1_1") (pintype "passive"))
      (node (ref "C7") (pin "1") (pinfunction "1_1") (pintype "passive"))
      (node (ref "C8") (pin "1") (pinfunction "1_1") (pintype "passive"))
      (node (ref "C9") (pin "1") (pinfunction "1_1") (pintype "passive"))
      (node (ref "CEC1") (pin "1") (pinfunction "1_1") (pintype "passive"))
      (node (ref "CEC1") (pin "2") (pinfunction "2_2") (pintype "passive"))
      (node (ref "CEC1") (pin "A12") (pinfunction "12_A12") (pintype "passive"))
      (node (ref "CEC1") (pin "A18") (pinfunction "18_A18") (pintype "passive"))
      (node (ref "CEC1") (pin "A24") (pinfunction "24_A24") (pintype "passive"))
      (node (ref "CEC1") (pin "A25") (pinfunction "25_A25") (pintype "passive"))
      (node (ref "CEC1") (pin "A26") (pinfunction "26_A26") (pintype "passive"))
      (node (ref "CEC1") (pin "A27") (pinfunction "27_A27") (pintype "passive"))
      (node (ref "CEC1") (pin "A28") (pinfunction "28_A28") (pintype "passive"))
      (node (ref "CEC1") (pin "A34") (pinfunction "34_A34") (pintype "passive"))
      (node (ref "CEC1") (pin "A39") (pinfunction "39_A39") (pintype "passive"))
      (node (ref "CEC1") (pin "B12") (pinfunction "12_B12") (pintype "passive"))
      (node (ref "CEC1") (pin "B18") (pinfunction "18_B18") (pintype "passive"))
      (node (ref "CEC1") (pin "B24") (pinfunction "24_B24") (pintype "passive"))
      (node (ref "CEC1") (pin "B25") (pinfunction "25_B25") (pintype "passive"))
      (node (ref "CEC1") (pin "B26") (pinfunction "26_B26") (pintype "passive"))
      (node (ref "CEC1") (pin "B27") (pinfunction "27_B27") (pintype "passive"))
      (node (ref "CEC1") (pin "B28") (pinfunction "28_B28") (pintype "passive"))
      (node (ref "CEC1") (pin "B34") (pinfunction "34_B34") (pintype "passive"))
      (node (ref "CEC1") (pin "B39") (pinfunction "39_B39") (pintype "passive"))
      (node (ref "CEC2") (pin "1") (pinfunction "1_1") (pintype "passive"))
      (node (ref "CEC2") (pin "2") (pinfunction "2_2") (pintype "passive"))
      (node (ref "CEC2") (pin "A12") (pinfunction "12_A12") (pintype "passive"))
      (node (ref "CEC2") (pin "A18") (pinfunction "18_A18") (pintype "passive"))
      (node (ref "CEC2") (pin "A24") (pinfunction "24_A24") (pintype "passive"))
      (node (ref "CEC2") (pin "A25") (pinfunction "25_A25") (pintype "passive"))
      (node (ref "CEC2") (pin "A26") (pinfunction "26_A26") (pintype "passive"))
      (node (ref "CEC2") (pin "A27") (pinfunction "27_A27") (pintype "passive"))
      (node (ref "CEC2") (pin "A28") (pinfunction "28_A28") (pintype "passive"))
      (node (ref "CEC2") (pin "A34") (pinfunction "34_A34") (pintype "passive"))
      (node (ref "CEC2") (pin "A39") (pinfunction "39_A39") (pintype "passive"))
      (node (ref "CEC2") (pin "B12") (pinfunction "12_B12") (pintype "passive"))
      (node (ref "CEC2") (pin "B18") (pinfunction "18_B18") (pintype "passive"))
      (node (ref "CEC2") (pin "B24") (pinfunction "24_B24") (pintype "passive"))
      (node (ref "CEC2") (pin "B25") (pinfunction "25_B25") (pintype "passive"))
      (node (ref "CEC2") (pin "B26") (pinfunction "26_B26") (pintype "passive"))
      (node (ref "CEC2") (pin "B27") (pinfunction "27_B27") (pintype "passive"))
      (node (ref "CEC2") (pin "B28") (pinfunction "28_B28") (pintype "passive"))
      (node (ref "CEC2") (pin "B34") (pinfunction "34_B34") (pintype "passive"))
      (node (ref "CEC2") (pin "B39") (pinfunction "39_B39") (pintype "passive"))
      (node (ref "IC1") (pin "107") (pinfunction "VSS_107") (pintype "power_in"))
      (node (ref "IC1") (pin "120") (pinfunction "VSS_120") (pintype "power_in"))
      (node (ref "IC1") (pin "130") (pinfunction "VSS_130") (pintype "power_in"))
      (node (ref "IC1") (pin "16") (pinfunction "VSS_16") (pintype "power_in"))
      (node (ref "IC1") (pin "31") (pinfunction "VSSA_31") (pintype "power_in"))
      (node (ref "IC1") (pin "38") (pinfunction "VSS_38") (pintype "power_in"))
      (node (ref "IC1") (pin "51") (pinfunction "VSS_51") (pintype "power_in"))
      (node (ref "IC1") (pin "61") (pinfunction "VSS_61") (pintype "power_in"))
      (node (ref "IC1") (pin "83") (pinfunction "VSS_83") (pintype "power_in"))
      (node (ref "IC1") (pin "94") (pinfunction "VSS_94") (pintype "power_in"))
      (node (ref "MH1") (pin "1") (pinfunction "1_1") (pintype "passive"))
      (node (ref "MH2") (pin "1") (pinfunction "1_1") (pintype "passive"))
      (node (ref "PB1") (pin "A") (pinfunction "A_A") (pintype "passive"))
      (node (ref "PB1") (pin "a") (pinfunction "a_a") (pintype "passive"))
      (node (ref "XTAL_C1") (pin "1") (pinfunction "1_1") (pintype "passive"))
      (node (ref "XTAL_C2") (pin "1") (pinfunction "1_1") (pintype "passive"))
    )
    (net (code "123") (name "Net-(XTAL1-Pad1)") (class "Default")
      (node (ref "XTAL1") (pin "1") (pinfunction "1_1") (pintype "passive"))
      (node (ref "XTAL_C2") (pin "2") (pinfunction "2_2") (pintype "passive"))
      (node (ref "XTAL_R1") (pin "1") (pinfunction "1_1") (pintype "passive"))
    )
    (net (code "124") (name "unconnected-(C24-Pad03)") (class "Default")
      (node (ref "C24") (pin "03") (pinfunction "03_03") (pintype "passive+no_connect"))
    )
    (net (code "125") (name "unconnected-(C24-Pad07)") (class "Default")
      (node (ref "C24") (pin "07") (pinfunction "07_07") (pintype "passive+no_connect"))
    )
    (net (code "126") (name "unconnected-(CEC1-40-PadB40)") (class "Default")
      (node (ref "CEC1") (pin "B40") (pinfunction "40_B40") (pintype "passive+no_connect"))
    )
    (net (code "127") (name "unconnected-(CEC1-41-PadB41)") (class "Default")
      (node (ref "CEC1") (pin "B41") (pinfunction "41_B41") (pintype "passive+no_connect"))
    )
    (net (code "128") (name "unconnected-(CEC1-42-PadB42)") (class "Default")
      (node (ref "CEC1") (pin "B42") (pinfunction "42_B42") (pintype "passive+no_connect"))
    )
    (net (code "129") (name "unconnected-(CEC2-38-PadA38)") (class "Default")
      (node (ref "CEC2") (pin "A38") (pinfunction "38_A38") (pintype "passive+no_connect"))
    )
    (net (code "130") (name "unconnected-(PB1-Padb)") (class "Default")
      (node (ref "PB1") (pin "b") (pinfunction "b_b") (pintype "passive+no_connect"))
    )
  )
)
